# probebase.net
KiCad netlist of a schematic drawn in EAGLE
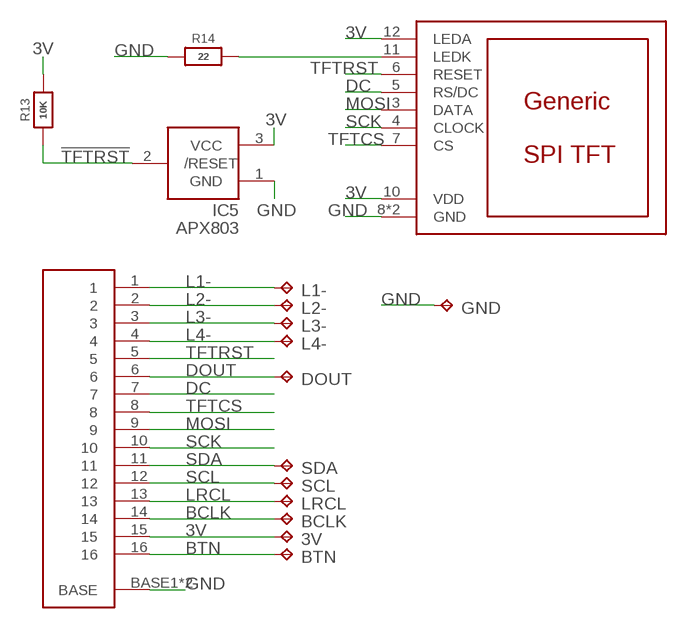
[diagram p0: schematic, sheet 1]

(export (version "E")
  (design (tool "Eeschema 10.0.6"))
  (components
    (comp (ref "3V")
      (value "TPTP14R")
      (footprint "eagle-import:TP14R")
      (libsource (lib "eagle-import") (part "TPTP14R"))
    )
    (comp (ref "BCLK")
      (value "TPTP14R")
      (footprint "eagle-import:TP14R")
      (libsource (lib "eagle-import") (part "TPTP14R"))
    )
    (comp (ref "BTN")
      (value "TPTP14R")
      (footprint "eagle-import:TP14R")
      (libsource (lib "eagle-import") (part "TPTP14R"))
    )
    (comp (ref "DOUT")
      (value "TPTP14R")
      (footprint "eagle-import:TP14R")
      (libsource (lib "eagle-import") (part "TPTP14R"))
    )
    (comp (ref "GND")
      (value "TPTP14R")
      (footprint "eagle-import:TP14R")
      (libsource (lib "eagle-import") (part "TPTP14R"))
    )
    (comp (ref "IC5")
      (value "APX803")
      (footprint "eagle-import:SOT23")
      (libsource (lib "eagle-import") (part "AXP083-SAG"))
    )
    (comp (ref "L1-")
      (value "TPTP14R")
      (footprint "eagle-import:TP14R")
      (libsource (lib "eagle-import") (part "TPTP14R"))
    )
    (comp (ref "L2-")
      (value "TPTP14R")
      (footprint "eagle-import:TP14R")
      (libsource (lib "eagle-import") (part "TPTP14R"))
    )
    (comp (ref "L3-")
      (value "TPTP14R")
      (footprint "eagle-import:TP14R")
      (libsource (lib "eagle-import") (part "TPTP14R"))
    )
    (comp (ref "L4-")
      (value "TPTP14R")
      (footprint "eagle-import:TP14R")
      (libsource (lib "eagle-import") (part "TPTP14R"))
    )
    (comp (ref "LRCL")
      (value "TPTP14R")
      (footprint "eagle-import:TP14R")
      (libsource (lib "eagle-import") (part "TPTP14R"))
    )
    (comp (ref "R13")
      (value "10K")
      (footprint "eagle-import:0603-NO")
      (libsource (lib "eagle-import") (part "RESISTOR_0603_NOOUT"))
    )
    (comp (ref "R14")
      (value "22")
      (footprint "eagle-import:0603-NO")
      (libsource (lib "eagle-import") (part "RESISTOR_0603_NOOUT"))
    )
    (comp (ref "SCL")
      (value "TPTP14R")
      (footprint "eagle-import:TP14R")
      (libsource (lib "eagle-import") (part "TPTP14R"))
    )
    (comp (ref "SDA")
      (value "TPTP14R")
      (footprint "eagle-import:TP14R")
      (libsource (lib "eagle-import") (part "TPTP14R"))
    )
    (comp (ref "U$3")
      (value "16PINFFC")
      (footprint "eagle-import:16PINFFC")
      (libsource (lib "eagle-import") (part "16PINFFC"))
    )
    (comp (ref "U$4")
      (value "TFT")
      (footprint "eagle-import:MICROBUILDER_TFT_1.14IN_240X135_WRAPUNDER")
      (libsource (lib "eagle-import") (part "TFT"))
    )
  )
  (nets
    (net (code "1") (name "/3V") (class "Default")
      (node (ref "3V") (pin "TP") (pinfunction "TP_TP") (pintype "input"))
      (node (ref "IC5") (pin "3") (pinfunction "VCC_3") (pintype "power_in"))
      (node (ref "R13") (pin "2") (pinfunction "2_2") (pintype "passive"))
      (node (ref "U$3") (pin "15") (pinfunction "15_15") (pintype "bidirectional"))
      (node (ref "U$4") (pin "10") (pinfunction "VDD_10") (pintype "power_in"))
      (node (ref "U$4") (pin "12") (pinfunction "LEDA_12") (pintype "input"))
    )
    (net (code "2") (name "/BCLK") (class "Default")
      (node (ref "BCLK") (pin "TP") (pinfunction "TP_TP") (pintype "input"))
      (node (ref "U$3") (pin "14") (pinfunction "14_14") (pintype "bidirectional"))
    )
    (net (code "3") (name "/BTN") (class "Default")
      (node (ref "BTN") (pin "TP") (pinfunction "TP_TP") (pintype "input"))
      (node (ref "U$3") (pin "16") (pinfunction "16_16") (pintype "bidirectional"))
    )
    (net (code "4") (name "/DC") (class "Default")
      (node (ref "U$3") (pin "7") (pinfunction "7_7") (pintype "bidirectional"))
      (node (ref "U$4") (pin "5") (pinfunction "RS/DC_5") (pintype "input"))
    )
    (net (code "5") (name "/DOUT") (class "Default")
      (node (ref "DOUT") (pin "TP") (pinfunction "TP_TP") (pintype "input"))
      (node (ref "U$3") (pin "6") (pinfunction "6_6") (pintype "bidirectional"))
    )
    (net (code "6") (name "/GND") (class "Default")
      (node (ref "GND") (pin "TP") (pinfunction "TP_TP") (pintype "input"))
      (node (ref "IC5") (pin "1") (pinfunction "GND_1") (pintype "power_in"))
      (node (ref "R14") (pin "1") (pinfunction "1_1") (pintype "passive"))
      (node (ref "U$3") (pin "BASE1") (pinfunction "BASE_BASE1") (pintype "bidirectional"))
      (node (ref "U$3") (pin "BASE2") (pinfunction "BASE_BASE2") (pintype "bidirectional"))
      (node (ref "U$4") (pin "13") (pinfunction "GND_13") (pintype "power_in"))
      (node (ref "U$4") (pin "8") (pinfunction "GND_8") (pintype "power_in"))
    )
    (net (code "7") (name "/L1-") (class "Default")
      (node (ref "L1-") (pin "TP") (pinfunction "TP_TP") (pintype "input"))
      (node (ref "U$3") (pin "1") (pinfunction "1_1") (pintype "bidirectional"))
    )
    (net (code "8") (name "/L2-") (class "Default")
      (node (ref "L2-") (pin "TP") (pinfunction "TP_TP") (pintype "input"))
      (node (ref "U$3") (pin "2") (pinfunction "2_2") (pintype "bidirectional"))
    )
    (net (code "9") (name "/L3-") (class "Default")
      (node (ref "L3-") (pin "TP") (pinfunction "TP_TP") (pintype "input"))
      (node (ref "U$3") (pin "3") (pinfunction "3_3") (pintype "bidirectional"))
    )
    (net (code "10") (name "/L4-") (class "Default")
      (node (ref "L4-") (pin "TP") (pinfunction "TP_TP") (pintype "input"))
      (node (ref "U$3") (pin "4") (pinfunction "4_4") (pintype "bidirectional"))
    )
    (net (code "11") (name "/LRCL") (class "Default")
      (node (ref "LRCL") (pin "TP") (pinfunction "TP_TP") (pintype "input"))
      (node (ref "U$3") (pin "13") (pinfunction "13_13") (pintype "bidirectional"))
    )
    (net (code "12") (name "/MOSI") (class "Default")
      (node (ref "U$3") (pin "9") (pinfunction "9_9") (pintype "bidirectional"))
      (node (ref "U$4") (pin "3") (pinfunction "DATA_3") (pintype "bidirectional"))
    )
    (net (code "13") (name "/SCK") (class "Default")
      (node (ref "U$3") (pin "10") (pinfunction "10_10") (pintype "bidirectional"))
      (node (ref "U$4") (pin "4") (pinfunction "CLOCK_4") (pintype "input"))
    )
    (net (code "14") (name "/SCL") (class "Default")
      (node (ref "SCL") (pin "TP") (pinfunction "TP_TP") (pintype "input"))
      (node (ref "U$3") (pin "12") (pinfunction "12_12") (pintype "bidirectional"))
    )
    (net (code "15") (name "/SDA") (class "Default")
      (node (ref "SDA") (pin "TP") (pinfunction "TP_TP") (pintype "input"))
      (node (ref "U$3") (pin "11") (pinfunction "11_11") (pintype "bidirectional"))
    )
    (net (code "16") (name "/TFTCS") (class "Default")
      (node (ref "U$3") (pin "8") (pinfunction "8_8") (pintype "bidirectional"))
      (node (ref "U$4") (pin "7") (pinfunction "CS_7") (pintype "input"))
    )
    (net (code "17") (name "/TFTRST") (class "Default")
      (node (ref "U$3") (pin "5") (pinfunction "5_5") (pintype "bidirectional"))
      (node (ref "U$4") (pin "6") (pinfunction "RESET_6") (pintype "input"))
    )
    (net (code "18") (name "/~{TFTRST}") (class "Default")
      (node (ref "IC5") (pin "2") (pinfunction "/RESET_2") (pintype "output"))
      (node (ref "R13") (pin "1") (pinfunction "1_1") (pintype "passive"))
    )
    (net (code "19") (name "Net-(U$4-LEDK)") (class "Default")
      (node (ref "R14") (pin "2") (pinfunction "2_2") (pintype "passive"))
      (node (ref "U$4") (pin "11") (pinfunction "LEDK_11") (pintype "input"))
    )
  )
)
